# Ethernet.net
KiCad netlist of a schematic drawn in Altium Designer
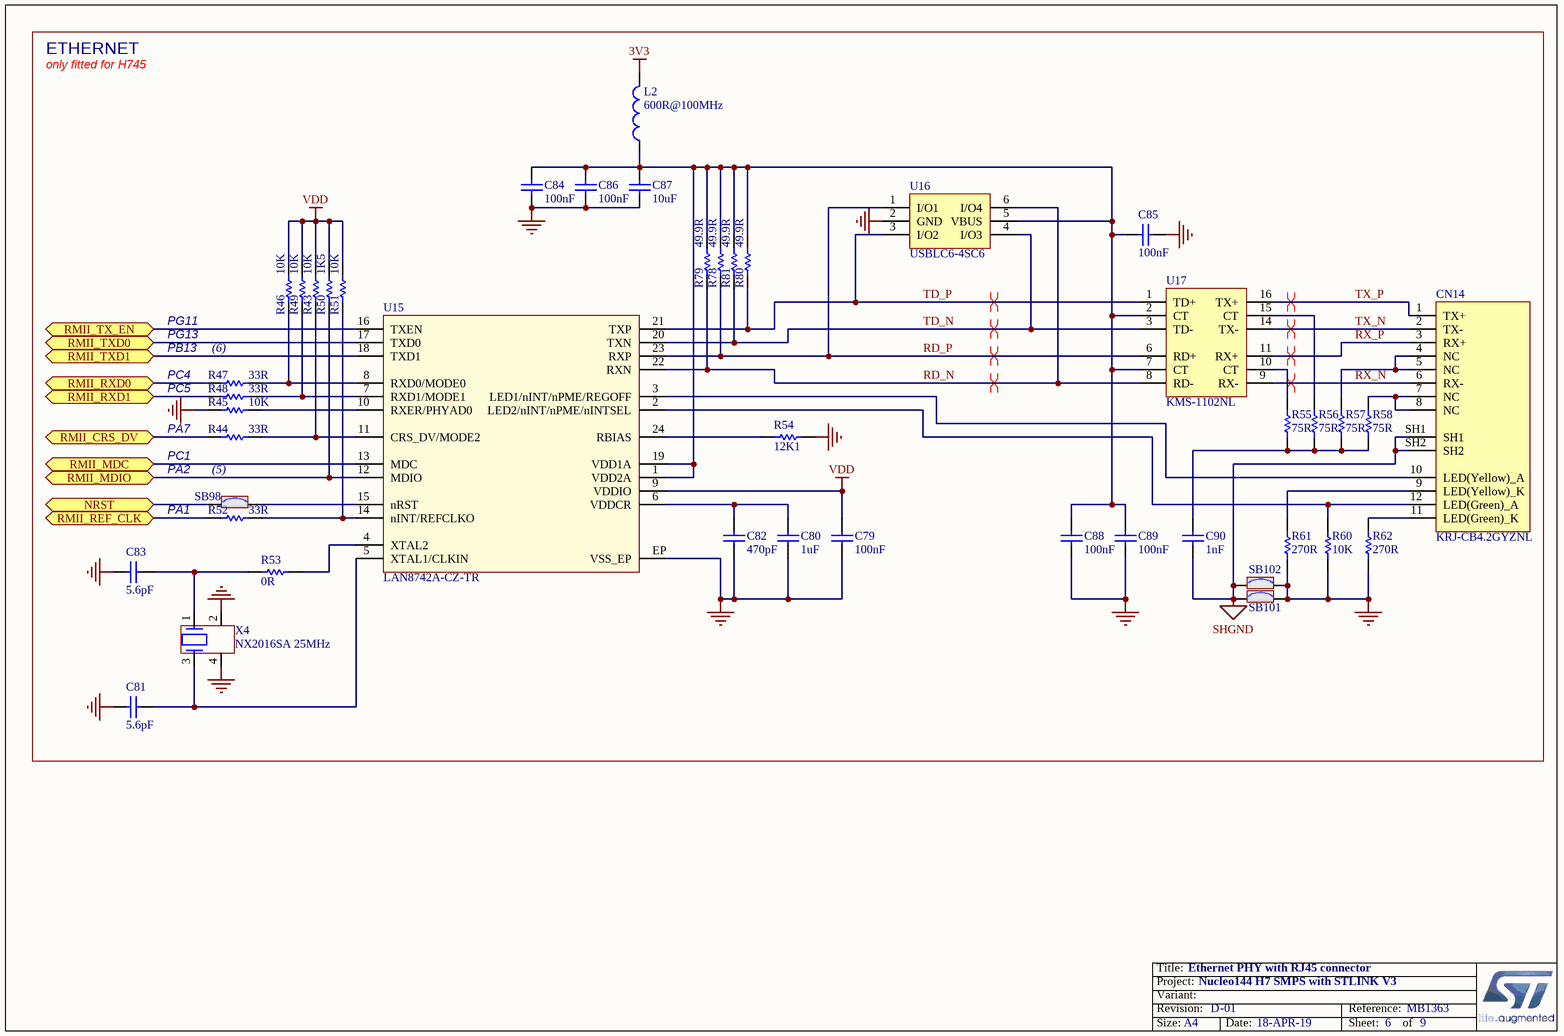
[diagram p0: Ethernet.SchDoc]

(export (version "E")
  (design (tool "Eeschema 10.0.6"))
  (components
    (comp (ref "C79")
      (value "100nF")
      (footprint "C0603")
      (description "Capacitor, MLCC, 100nF, 6V3, X5R, 10%, 0603, T=0,8mm")
      (fields
        (field (name "INTERNAL_PART_NUMBER") "MCD-00237")
        (field (name "MANUFACTURER_PART_NUMBER") "CC0603KRX5R5BB104")
        (field (name "PROVIDED_BY") "SUBCO")
      )
      (libsource (lib "MCD_PARTS_database") (part "Capacitor"))
    )
    (comp (ref "C80")
      (value "1uF")
      (footprint "C0402")
      (description "Capacitor, MLCC, 1uF, 6V3, X5R, 10%, 0402, T=0,5mm")
      (fields
        (field (name "INTERNAL_PART_NUMBER") "MCD-00095")
        (field (name "MANUFACTURER_PART_NUMBER") "GRM155R61E105KA12")
        (field (name "PROVIDED_BY") "SUBCO")
      )
      (libsource (lib "MCD_PARTS_database") (part "Capacitor"))
    )
    (comp (ref "C81")
      (value "5.6pF")
      (footprint "C0402")
      (description "Capacitor, MLCC, 5.6pF, 50V, NPO, 5%, 0402, T=0,5mm")
      (fields
        (field (name "INTERNAL_PART_NUMBER") "MCD-01374")
        (field (name "MANUFACTURER_PART_NUMBER") "CC0402BRNPO9BN5R6")
        (field (name "PROVIDED_BY") "SUBCO")
      )
      (libsource (lib "MCD_PARTS_database") (part "Capacitor"))
    )
    (comp (ref "C82")
      (value "470pF")
      (footprint "C0402")
      (description "Capacitor, MLCC, 470pF, 50V, NPO, 5%, 0402, T=0,5mm")
      (fields
        (field (name "INTERNAL_PART_NUMBER") "MCD-00724")
        (field (name "MANUFACTURER_PART_NUMBER") "CC0402JRNPO9BN471")
        (field (name "PROVIDED_BY") "SUBCO")
      )
      (libsource (lib "MCD_PARTS_database") (part "Capacitor"))
    )
    (comp (ref "C83")
      (value "5.6pF")
      (footprint "C0402")
      (description "Capacitor, MLCC, 5.6pF, 50V, NPO, 5%, 0402, T=0,5mm")
      (fields
        (field (name "INTERNAL_PART_NUMBER") "MCD-01374")
        (field (name "MANUFACTURER_PART_NUMBER") "CC0402BRNPO9BN5R6")
        (field (name "PROVIDED_BY") "SUBCO")
      )
      (libsource (lib "MCD_PARTS_database") (part "Capacitor"))
    )
    (comp (ref "C84")
      (value "100nF")
      (footprint "C0603")
      (description "Capacitor, MLCC, 100nF, 6V3, X5R, 10%, 0603, T=0,8mm")
      (fields
        (field (name "INTERNAL_PART_NUMBER") "MCD-00237")
        (field (name "MANUFACTURER_PART_NUMBER") "CC0603KRX5R5BB104")
        (field (name "PROVIDED_BY") "SUBCO")
      )
      (libsource (lib "MCD_PARTS_database") (part "Capacitor"))
    )
    (comp (ref "C85")
      (value "100nF")
      (footprint "C0603")
      (description "Capacitor, MLCC, 100nF, 6V3, X5R, 10%, 0603, T=0,8mm")
      (fields
        (field (name "INTERNAL_PART_NUMBER") "MCD-00237")
        (field (name "MANUFACTURER_PART_NUMBER") "CC0603KRX5R5BB104")
        (field (name "PROVIDED_BY") "SUBCO")
      )
      (libsource (lib "MCD_PARTS_database") (part "Capacitor"))
    )
    (comp (ref "C86")
      (value "100nF")
      (footprint "C0603")
      (description "Capacitor, MLCC, 100nF, 6V3, X5R, 10%, 0603, T=0,8mm")
      (fields
        (field (name "INTERNAL_PART_NUMBER") "MCD-00237")
        (field (name "MANUFACTURER_PART_NUMBER") "CC0603KRX5R5BB104")
        (field (name "PROVIDED_BY") "SUBCO")
      )
      (libsource (lib "MCD_PARTS_database") (part "Capacitor"))
    )
    (comp (ref "C87")
      (value "10uF")
      (footprint "C0603")
      (description "Capacitor, MLCC, 10µF, 10V, X5R, 10%, 0603, T=0.8mm")
      (fields
        (field (name "INTERNAL_PART_NUMBER") "MCD-01124")
        (field (name "MANUFACTURER_PART_NUMBER") "GRM188R61A106KAAL")
        (field (name "PROVIDED_BY") "SUBCO")
      )
      (libsource (lib "MCD_PARTS_database") (part "Capacitor"))
    )
    (comp (ref "C88")
      (value "100nF")
      (footprint "C0603")
      (description "Capacitor, MLCC, 100nF, 6V3, X5R, 10%, 0603, T=0,8mm")
      (fields
        (field (name "INTERNAL_PART_NUMBER") "MCD-00237")
        (field (name "MANUFACTURER_PART_NUMBER") "CC0603KRX5R5BB104")
        (field (name "PROVIDED_BY") "SUBCO")
      )
      (libsource (lib "MCD_PARTS_database") (part "Capacitor"))
    )
    (comp (ref "C89")
      (value "100nF")
      (footprint "C0603")
      (description "Capacitor, MLCC, 100nF, 6V3, X5R, 10%, 0603, T=0,8mm")
      (fields
        (field (name "INTERNAL_PART_NUMBER") "MCD-00237")
        (field (name "MANUFACTURER_PART_NUMBER") "CC0603KRX5R5BB104")
        (field (name "PROVIDED_BY") "SUBCO")
      )
      (libsource (lib "MCD_PARTS_database") (part "Capacitor"))
    )
    (comp (ref "C90")
      (value "1nF")
      (footprint "C1206_H1P6")
      (description "Capacitor, MLCC, 1nF, 2KV, X7R, 10%, 1206, T=1,25mm")
      (fields
        (field (name "INTERNAL_PART_NUMBER") "MCD-00722")
        (field (name "MANUFACTURER_PART_NUMBER") "CC1206KKX7RDBB102")
        (field (name "PROVIDED_BY") "SUBCO")
      )
      (libsource (lib "MCD_PARTS_database") (part "Capacitor"))
    )
    (comp (ref "CN14")
      (value "KRJ-CB4.2GYZNL")
      (footprint "CON_RJ45_DGKYD_KRJ-CB4.2GYZNL")
      (description "RJ45 jack, single port, with LEDS, Metal shielded dip low profile")
      (fields
        (field (name "INTERNAL_PART_NUMBER") "MCD-00717")
        (field (name "MANUFACTURER") "DONGGUAN KEYOUDA ELECTRONIC TECHNOLOGY")
        (field (name "PROVIDED_BY") "SUBCO")
      )
      (libsource (lib "MCD_PARTS_database") (part "RJ45_KRJ-CB4.2GYZNL"))
    )
    (comp (ref "L2")
      (value "600R@100MHz")
      (footprint "L0603")
      (description "SMD Chip ferrite bead, 600R@100MHz +/-25%, 350mA, 500mohm DC, 0603, T=0.8mm")
      (fields
        (field (name "INTERNAL_PART_NUMBER") "MCD-00047")
        (field (name "MANUFACTURER_PART_NUMBER") "FCM1608KF-601T03")
        (field (name "PROVIDED_BY") "SUBCO")
      )
      (libsource (lib "MCD_PARTS_database") (part "BEAD"))
    )
    (comp (ref "R43")
      (value "10K")
      (footprint "R0402")
      (description "Resistor,10K,0402,1%,1/16W")
      (fields
        (field (name "INTERNAL_PART_NUMBER") "MCD-00053")
        (field (name "MANUFACTURER_PART_NUMBER") "RC0402FR-0710KL")
        (field (name "PROVIDED_BY") "SUBCO")
      )
      (libsource (lib "MCD_PARTS_database") (part "Resistor"))
    )
    (comp (ref "R44")
      (value "33R")
      (footprint "R0402")
      (description "Resistor,33R,0402,1%,1/16W")
      (fields
        (field (name "INTERNAL_PART_NUMBER") "MCD-00455")
        (field (name "MANUFACTURER_PART_NUMBER") "RC0402FR-0733RL")
        (field (name "PROVIDED_BY") "SUBCO")
      )
      (libsource (lib "MCD_PARTS_database") (part "Resistor"))
    )
    (comp (ref "R45")
      (value "10K")
      (footprint "R0402")
      (description "Resistor,10K,0402,1%,1/16W")
      (fields
        (field (name "INTERNAL_PART_NUMBER") "MCD-00053")
        (field (name "MANUFACTURER_PART_NUMBER") "RC0402FR-0710KL")
        (field (name "PROVIDED_BY") "SUBCO")
      )
      (libsource (lib "MCD_PARTS_database") (part "Resistor"))
    )
    (comp (ref "R46")
      (value "10K")
      (footprint "R0402")
      (description "Resistor,10K,0402,1%,1/16W")
      (fields
        (field (name "INTERNAL_PART_NUMBER") "MCD-00053")
        (field (name "MANUFACTURER_PART_NUMBER") "RC0402FR-0710KL")
        (field (name "PROVIDED_BY") "SUBCO")
      )
      (libsource (lib "MCD_PARTS_database") (part "Resistor"))
    )
    (comp (ref "R47")
      (value "33R")
      (footprint "R0402")
      (description "Resistor,33R,0402,1%,1/16W")
      (fields
        (field (name "INTERNAL_PART_NUMBER") "MCD-00455")
        (field (name "MANUFACTURER_PART_NUMBER") "RC0402FR-0733RL")
        (field (name "PROVIDED_BY") "SUBCO")
      )
      (libsource (lib "MCD_PARTS_database") (part "Resistor"))
    )
    (comp (ref "R48")
      (value "33R")
      (footprint "R0402")
      (description "Resistor,33R,0402,1%,1/16W")
      (fields
        (field (name "INTERNAL_PART_NUMBER") "MCD-00455")
        (field (name "MANUFACTURER_PART_NUMBER") "RC0402FR-0733RL")
        (field (name "PROVIDED_BY") "SUBCO")
      )
      (libsource (lib "MCD_PARTS_database") (part "Resistor"))
    )
    (comp (ref "R49")
      (value "10K")
      (footprint "R0402")
      (description "Resistor,10K,0402,1%,1/16W")
      (fields
        (field (name "INTERNAL_PART_NUMBER") "MCD-00053")
        (field (name "MANUFACTURER_PART_NUMBER") "RC0402FR-0710KL")
        (field (name "PROVIDED_BY") "SUBCO")
      )
      (libsource (lib "MCD_PARTS_database") (part "Resistor"))
    )
    (comp (ref "R50")
      (value "1K5")
      (footprint "R0402")
      (description "Resistor,1K5,0402,1%,1/16W")
      (fields
        (field (name "INTERNAL_PART_NUMBER") "MCD-00068")
        (field (name "MANUFACTURER_PART_NUMBER") "RC0402FR-071K5L")
        (field (name "PROVIDED_BY") "SUBCO")
      )
      (libsource (lib "MCD_PARTS_database") (part "Resistor"))
    )
    (comp (ref "R51")
      (value "10K")
      (footprint "R0402")
      (description "Resistor,10K,0402,1%,1/16W")
      (fields
        (field (name "INTERNAL_PART_NUMBER") "MCD-00053")
        (field (name "MANUFACTURER_PART_NUMBER") "RC0402FR-0710KL")
        (field (name "PROVIDED_BY") "SUBCO")
      )
      (libsource (lib "MCD_PARTS_database") (part "Resistor"))
    )
    (comp (ref "R52")
      (value "33R")
      (footprint "R0402")
      (description "Resistor,33R,0402,1%,1/16W")
      (fields
        (field (name "INTERNAL_PART_NUMBER") "MCD-00455")
        (field (name "MANUFACTURER_PART_NUMBER") "RC0402FR-0733RL")
        (field (name "PROVIDED_BY") "SUBCO")
      )
      (libsource (lib "MCD_PARTS_database") (part "Resistor"))
    )
    (comp (ref "R53")
      (value "0R")
      (footprint "R0402")
      (description "Resistor,0R,0402,5%,1/16W")
      (fields
        (field (name "INTERNAL_PART_NUMBER") "MCD-00052")
        (field (name "MANUFACTURER_PART_NUMBER") "RC0402JR-070RL")
        (field (name "PROVIDED_BY") "SUBCO")
      )
      (libsource (lib "MCD_PARTS_database") (part "Resistor"))
    )
    (comp (ref "R54")
      (value "12K1")
      (footprint "R0402")
      (description "Resistor,12K1,0402,1%,1/16W")
      (fields
        (field (name "INTERNAL_PART_NUMBER") "MCD-00723")
        (field (name "MANUFACTURER_PART_NUMBER") "RC0402FR-0712K1L")
        (field (name "PROVIDED_BY") "SUBCO")
      )
      (libsource (lib "MCD_PARTS_database") (part "Resistor"))
    )
    (comp (ref "R55")
      (value "75R")
      (footprint "R0402")
      (description "Resistor,75R,0402,1%,1/16W")
      (fields
        (field (name "INTERNAL_PART_NUMBER") "MCD-00515")
        (field (name "MANUFACTURER_PART_NUMBER") "RC0402FR-0775RL")
        (field (name "PROVIDED_BY") "SUBCO")
      )
      (libsource (lib "MCD_PARTS_database") (part "Resistor"))
    )
    (comp (ref "R56")
      (value "75R")
      (footprint "R0402")
      (description "Resistor,75R,0402,1%,1/16W")
      (fields
        (field (name "INTERNAL_PART_NUMBER") "MCD-00515")
        (field (name "MANUFACTURER_PART_NUMBER") "RC0402FR-0775RL")
        (field (name "PROVIDED_BY") "SUBCO")
      )
      (libsource (lib "MCD_PARTS_database") (part "Resistor"))
    )
    (comp (ref "R57")
      (value "75R")
      (footprint "R0402")
      (description "Resistor,75R,0402,1%,1/16W")
      (fields
        (field (name "INTERNAL_PART_NUMBER") "MCD-00515")
        (field (name "MANUFACTURER_PART_NUMBER") "RC0402FR-0775RL")
        (field (name "PROVIDED_BY") "SUBCO")
      )
      (libsource (lib "MCD_PARTS_database") (part "Resistor"))
    )
    (comp (ref "R58")
      (value "75R")
      (footprint "R0402")
      (description "Resistor,75R,0402,1%,1/16W")
      (fields
        (field (name "INTERNAL_PART_NUMBER") "MCD-00515")
        (field (name "MANUFACTURER_PART_NUMBER") "RC0402FR-0775RL")
        (field (name "PROVIDED_BY") "SUBCO")
      )
      (libsource (lib "MCD_PARTS_database") (part "Resistor"))
    )
    (comp (ref "R60")
      (value "10K")
      (footprint "R0402")
      (description "Resistor,10K,0402,1%,1/16W")
      (fields
        (field (name "INTERNAL_PART_NUMBER") "MCD-00053")
        (field (name "MANUFACTURER_PART_NUMBER") "RC0402FR-0710KL")
        (field (name "PROVIDED_BY") "SUBCO")
      )
      (libsource (lib "MCD_PARTS_database") (part "Resistor"))
    )
    (comp (ref "R61")
      (value "270R")
      (footprint "R0402")
      (description "Resistor,270R,0402,1%,1/16W")
      (fields
        (field (name "INTERNAL_PART_NUMBER") "MCD-00441")
        (field (name "MANUFACTURER_PART_NUMBER") "RC0402FR-07270RL")
        (field (name "PROVIDED_BY") "SUBCO")
      )
      (libsource (lib "MCD_PARTS_database") (part "Resistor"))
    )
    (comp (ref "R62")
      (value "270R")
      (footprint "R0402")
      (description "Resistor,270R,0402,1%,1/16W")
      (fields
        (field (name "INTERNAL_PART_NUMBER") "MCD-00441")
        (field (name "MANUFACTURER_PART_NUMBER") "RC0402FR-07270RL")
        (field (name "PROVIDED_BY") "SUBCO")
      )
      (libsource (lib "MCD_PARTS_database") (part "Resistor"))
    )
    (comp (ref "R78")
      (value "49.9R")
      (footprint "R0402")
      (description "Resistor,49R9,0402,1%,1/16W")
      (fields
        (field (name "INTERNAL_PART_NUMBER") "MCD-00565")
        (field (name "MANUFACTURER_PART_NUMBER") "RC0402FR-0749R9L")
        (field (name "PROVIDED_BY") "SUBCO")
      )
      (libsource (lib "MCD_PARTS_database") (part "Resistor"))
    )
    (comp (ref "R79")
      (value "49.9R")
      (footprint "R0402")
      (description "Resistor,49R9,0402,1%,1/16W")
      (fields
        (field (name "INTERNAL_PART_NUMBER") "MCD-00565")
        (field (name "MANUFACTURER_PART_NUMBER") "RC0402FR-0749R9L")
        (field (name "PROVIDED_BY") "SUBCO")
      )
      (libsource (lib "MCD_PARTS_database") (part "Resistor"))
    )
    (comp (ref "R80")
      (value "49.9R")
      (footprint "R0402")
      (description "Resistor,49R9,0402,1%,1/16W")
      (fields
        (field (name "INTERNAL_PART_NUMBER") "MCD-00565")
        (field (name "MANUFACTURER_PART_NUMBER") "RC0402FR-0749R9L")
        (field (name "PROVIDED_BY") "SUBCO")
      )
      (libsource (lib "MCD_PARTS_database") (part "Resistor"))
    )
    (comp (ref "R81")
      (value "49.9R")
      (footprint "R0402")
      (description "Resistor,49R9,0402,1%,1/16W")
      (fields
        (field (name "INTERNAL_PART_NUMBER") "MCD-00565")
        (field (name "MANUFACTURER_PART_NUMBER") "RC0402FR-0749R9L")
        (field (name "PROVIDED_BY") "SUBCO")
      )
      (libsource (lib "MCD_PARTS_database") (part "Resistor"))
    )
    (comp (ref "SB98")
      (value "SB_ON")
      (footprint "SOLDER-BRIDGE_R0603-0R")
      (description "Solder Bridge ON")
      (fields
        (field (name "INTERNAL_PART_NUMBER") "MCD-00071")
        (field (name "MANUFACTURER_PART_NUMBER") "RC0603JR-070RL")
        (field (name "PROVIDED_BY") "SUBCO")
      )
      (libsource (lib "MCD_PARTS_database") (part "SB_ON"))
    )
    (comp (ref "SB101")
      (value "SB_ON")
      (footprint "SOLDER-BRIDGE_R0603-0R")
      (description "Solder Bridge ON")
      (fields
        (field (name "INTERNAL_PART_NUMBER") "MCD-00071")
        (field (name "MANUFACTURER_PART_NUMBER") "RC0603JR-070RL")
        (field (name "PROVIDED_BY") "SUBCO")
      )
      (libsource (lib "MCD_PARTS_database") (part "SB_ON"))
    )
    (comp (ref "SB102")
      (value "SB_ON")
      (footprint "SOLDER-BRIDGE_R0603-0R")
      (description "Solder Bridge ON")
      (fields
        (field (name "INTERNAL_PART_NUMBER") "MCD-00071")
        (field (name "MANUFACTURER_PART_NUMBER") "RC0603JR-070RL")
        (field (name "PROVIDED_BY") "SUBCO")
      )
      (libsource (lib "MCD_PARTS_database") (part "SB_ON"))
    )
    (comp (ref "U15")
      (value "LAN8742A-CZ-TR")
      (footprint "ICC_VQFN24-EPAD_4X4_P050")
      (description "10/100M RMII Ethernet transceiver")
      (fields
        (field (name "INTERNAL_PART_NUMBER") "MCD-00719")
        (field (name "MANUFACTURER") "MICROCHIP")
        (field (name "PROVIDED_BY") "SUBCO")
      )
      (libsource (lib "MCD_PARTS_database") (part "LAN8742A-CZ-TR"))
    )
    (comp (ref "U16")
      (value "USBLC6-4SC6")
      (footprint "ESD_SOT23-6L")
      (description "Very low capacitance ESD protection , 4 lines")
      (fields
        (field (name "INTERNAL_PART_NUMBER") "MCD-00250")
        (field (name "MANUFACTURER") "STMICROELECTRONICS")
        (field (name "PROVIDED_BY") "SUBCO with ST control")
      )
      (libsource (lib "MCD_PARTS_database") (part "USBLC6-4SC6"))
    )
    (comp (ref "U17")
      (value "KMS-1102NL")
      (footprint "TRS_DGKYD_KMS-1102NL")
      (description "Discrete Magnetic Transformer Module, 16 pins, SMT, 100 Base-TX")
      (fields
        (field (name "INTERNAL_PART_NUMBER") "MCD-00718")
        (field (name "MANUFACTURER") "DONGGUAN KEYOUDA ELECTRONIC TECHNOLOGY")
        (field (name "PROVIDED_BY") "SUBCO")
      )
      (libsource (lib "MCD_PARTS_database") (part "KMS-1102NL"))
    )
    (comp (ref "X4")
      (value "NX2016SA 25MHz")
      (footprint "CRY_NX2016SA_4P")
      (description "Crystal 25MHz, 6pF, +-20ppm, 80ohms max, SMD")
      (fields
        (field (name "INTERNAL_PART_NUMBER") "MCD-01364")
        (field (name "MANUFACTURER_PART_NUMBER") "NX2016SA 25MHz EXS00A-CS11321")
        (field (name "PROVIDED_BY") "SUBCO")
      )
      (libsource (lib "MCD_PARTS_database") (part "XTAL_4_PINS"))
    )
  )
  (nets
    (net (code "1") (name "/NRST") (class "Default")
      (node (ref "SB98") (pin "1") (pinfunction "1_1") (pintype "passive"))
    )
    (net (code "2") (name "/RD_N") (class "Default")
      (node (ref "R79") (pin "1") (pinfunction "1_1") (pintype "passive"))
      (node (ref "U15") (pin "22") (pinfunction "RXN_22") (pintype "passive"))
      (node (ref "U16") (pin "6") (pinfunction "I/O4_6") (pintype "passive"))
      (node (ref "U17") (pin "8") (pinfunction "RD-_8") (pintype "passive"))
    )
    (net (code "3") (name "/RD_P") (class "Default")
      (node (ref "R78") (pin "1") (pinfunction "1_1") (pintype "passive"))
      (node (ref "U15") (pin "23") (pinfunction "RXP_23") (pintype "passive"))
      (node (ref "U16") (pin "1") (pinfunction "I/O1_1") (pintype "passive"))
      (node (ref "U17") (pin "6") (pinfunction "RD+_6") (pintype "passive"))
    )
    (net (code "4") (name "/RMII_CRS_DV") (class "Default")
      (node (ref "R44") (pin "1") (pinfunction "1_1") (pintype "passive"))
    )
    (net (code "5") (name "/RMII_MDC") (class "Default")
      (node (ref "U15") (pin "13") (pinfunction "MDC_13") (pintype "passive"))
    )
    (net (code "6") (name "/RMII_MDIO") (class "Default")
      (node (ref "R50") (pin "1") (pinfunction "1_1") (pintype "passive"))
      (node (ref "U15") (pin "12") (pinfunction "MDIO_12") (pintype "passive"))
    )
    (net (code "7") (name "/RMII_REF_CLK") (class "Default")
      (node (ref "R52") (pin "1") (pinfunction "1_1") (pintype "passive"))
    )
    (net (code "8") (name "/RMII_RXD0") (class "Default")
      (node (ref "R47") (pin "1") (pinfunction "1_1") (pintype "passive"))
    )
    (net (code "9") (name "/RMII_RXD1") (class "Default")
      (node (ref "R48") (pin "1") (pinfunction "1_1") (pintype "passive"))
    )
    (net (code "10") (name "/RMII_TXD0") (class "Default")
      (node (ref "U15") (pin "17") (pinfunction "TXD0_17") (pintype "passive"))
    )
    (net (code "11") (name "/RMII_TXD1") (class "Default")
      (node (ref "U15") (pin "18") (pinfunction "TXD1_18") (pintype "passive"))
    )
    (net (code "12") (name "/RMII_TX_EN") (class "Default")
      (node (ref "U15") (pin "16") (pinfunction "TXEN_16") (pintype "passive"))
    )
    (net (code "13") (name "/RX_N") (class "Default")
      (node (ref "CN14") (pin "6") (pinfunction "RX-_6") (pintype "passive"))
      (node (ref "U17") (pin "9") (pinfunction "RX-_9") (pintype "passive"))
    )
    (net (code "14") (name "/RX_P") (class "Default")
      (node (ref "CN14") (pin "3") (pinfunction "RX+_3") (pintype "passive"))
      (node (ref "U17") (pin "11") (pinfunction "RX+_11") (pintype "passive"))
    )
    (net (code "15") (name "/TD_N") (class "Default")
      (node (ref "R81") (pin "1") (pinfunction "1_1") (pintype "passive"))
      (node (ref "U15") (pin "20") (pinfunction "TXN_20") (pintype "passive"))
      (node (ref "U16") (pin "4") (pinfunction "I/O3_4") (pintype "passive"))
      (node (ref "U17") (pin "3") (pinfunction "TD-_3") (pintype "passive"))
    )
    (net (code "16") (name "/TD_P") (class "Default")
      (node (ref "R80") (pin "1") (pinfunction "1_1") (pintype "passive"))
      (node (ref "U15") (pin "21") (pinfunction "TXP_21") (pintype "passive"))
      (node (ref "U16") (pin "3") (pinfunction "I/O2_3") (pintype "passive"))
      (node (ref "U17") (pin "1") (pinfunction "TD+_1") (pintype "passive"))
    )
    (net (code "17") (name "/TX_N") (class "Default")
      (node (ref "CN14") (pin "2") (pinfunction "TX-_2") (pintype "passive"))
      (node (ref "U17") (pin "14") (pinfunction "TX-_14") (pintype "passive"))
    )
    (net (code "18") (name "/TX_P") (class "Default")
      (node (ref "CN14") (pin "1") (pinfunction "TX+_1") (pintype "passive"))
      (node (ref "U17") (pin "16") (pinfunction "TX+_16") (pintype "passive"))
    )
    (net (code "19") (name "3V3") (class "Default")
      (node (ref "L2") (pin "2") (pinfunction "2_2") (pintype "passive"))
    )
    (net (code "20") (name "GND") (class "Default")
      (node (ref "C79") (pin "1") (pinfunction "1_1") (pintype "passive"))
      (node (ref "C80") (pin "1") (pinfunction "1_1") (pintype "passive"))
      (node (ref "C81") (pin "1") (pinfunction "1_1") (pintype "passive"))
      (node (ref "C82") (pin "1") (pinfunction "1_1") (pintype "passive"))
      (node (ref "C83") (pin "1") (pinfunction "1_1") (pintype "passive"))
      (node (ref "C84") (pin "1") (pinfunction "1_1") (pintype "passive"))
      (node (ref "C85") (pin "2") (pinfunction "2_2") (pintype "passive"))
      (node (ref "C86") (pin "1") (pinfunction "1_1") (pintype "passive"))
      (node (ref "C87") (pin "1") (pinfunction "1_1") (pintype "passive"))
      (node (ref "C88") (pin "1") (pinfunction "1_1") (pintype "passive"))
      (node (ref "C89") (pin "1") (pinfunction "1_1") (pintype "passive"))
      (node (ref "R45") (pin "2") (pinfunction "2_2") (pintype "passive"))
      (node (ref "R54") (pin "2") (pinfunction "2_2") (pintype "passive"))
      (node (ref "R60") (pin "1") (pinfunction "1_1") (pintype "passive"))
      (node (ref "R61") (pin "1") (pinfunction "1_1") (pintype "passive"))
      (node (ref "R62") (pin "1") (pinfunction "1_1") (pintype "passive"))
      (node (ref "SB101") (pin "2") (pinfunction "2_2") (pintype "passive"))
      (node (ref "SB102") (pin "2") (pinfunction "2_2") (pintype "passive"))
      (node (ref "U15") (pin "EP") (pinfunction "VSS_EP_EP") (pintype "passive"))
      (node (ref "U16") (pin "2") (pinfunction "GND_2") (pintype "passive"))
      (node (ref "X4") (pin "2") (pinfunction "2_2") (pintype "passive"))
      (node (ref "X4") (pin "4") (pinfunction "4_4") (pintype "passive"))
    )
    (net (code "21") (name "Net-(C83-Pad2)") (class "Default")
      (node (ref "C83") (pin "2") (pinfunction "2_2") (pintype "passive"))
      (node (ref "R53") (pin "1") (pinfunction "1_1") (pintype "passive"))
      (node (ref "X4") (pin "1") (pinfunction "1_1") (pintype "passive"))
    )
    (net (code "22") (name "Net-(C90-Pad2)") (class "Default")
      (node (ref "C90") (pin "2") (pinfunction "2_2") (pintype "passive"))
      (node (ref "R55") (pin "1") (pinfunction "1_1") (pintype "passive"))
      (node (ref "R56") (pin "1") (pinfunction "1_1") (pintype "passive"))
      (node (ref "R57") (pin "1") (pinfunction "1_1") (pintype "passive"))
      (node (ref "R58") (pin "1") (pinfunction "1_1") (pintype "passive"))
    )
    (net (code "23") (name "Net-(CN14-LED(Green)_A)") (class "Default")
      (node (ref "CN14") (pin "12") (pinfunction "LED(Green)_A_12") (pintype "passive"))
      (node (ref "R60") (pin "2") (pinfunction "2_2") (pintype "passive"))
      (node (ref "U15") (pin "2") (pinfunction "LED2/nINT/nPME/nINTSEL_2") (pintype "passive"))
    )
    (net (code "24") (name "Net-(CN14-LED(Green)_K)") (class "Default")
      (node (ref "CN14") (pin "11") (pinfunction "LED(Green)_K_11") (pintype "passive"))
      (node (ref "R62") (pin "2") (pinfunction "2_2") (pintype "passive"))
    )
    (net (code "25") (name "Net-(CN14-LED(Yellow)_A)") (class "Default")
      (node (ref "CN14") (pin "10") (pinfunction "LED(Yellow)_A_10") (pintype "passive"))
      (node (ref "U15") (pin "3") (pinfunction "LED1/nINT/nPME/REGOFF_3") (pintype "passive"))
    )
    (net (code "26") (name "Net-(CN14-LED(Yellow)_K)") (class "Default")
      (node (ref "CN14") (pin "9") (pinfunction "LED(Yellow)_K_9") (pintype "passive"))
      (node (ref "R61") (pin "2") (pinfunction "2_2") (pintype "passive"))
    )
    (net (code "27") (name "Net-(CN14-NC-Pad4)") (class "Default")
      (node (ref "CN14") (pin "4") (pinfunction "NC_4") (pintype "passive"))
      (node (ref "CN14") (pin "5") (pinfunction "NC_5") (pintype "passive"))
      (node (ref "R57") (pin "2") (pinfunction "2_2") (pintype "passive"))
    )
    (net (code "28") (name "Net-(CN14-NC-Pad7)") (class "Default")
      (node (ref "CN14") (pin "7") (pinfunction "NC_7") (pintype "passive"))
      (node (ref "CN14") (pin "8") (pinfunction "NC_8") (pintype "passive"))
      (node (ref "R58") (pin "2") (pinfunction "2_2") (pintype "passive"))
    )
    (net (code "29") (name "Net-(R55-Pad2)") (class "Default")
      (node (ref "R55") (pin "2") (pinfunction "2_2") (pintype "passive"))
      (node (ref "U17") (pin "10") (pinfunction "CT_10") (pintype "passive"))
    )
    (net (code "30") (name "Net-(R56-Pad2)") (class "Default")
      (node (ref "R56") (pin "2") (pinfunction "2_2") (pintype "passive"))
      (node (ref "U17") (pin "15") (pinfunction "CT_15") (pintype "passive"))
    )
    (net (code "31") (name "Net-(U15-CRS_DV{slash}MODE2)") (class "Default")
      (node (ref "R43") (pin "1") (pinfunction "1_1") (pintype "passive"))
      (node (ref "R44") (pin "2") (pinfunction "2_2") (pintype "passive"))
      (node (ref "U15") (pin "11") (pinfunction "CRS_DV/MODE2_11") (pintype "passive"))
    )
    (net (code "32") (name "Net-(U15-RBIAS)") (class "Default")
      (node (ref "R54") (pin "1") (pinfunction "1_1") (pintype "passive"))
      (node (ref "U15") (pin "24") (pinfunction "RBIAS_24") (pintype "passive"))
    )
    (net (code "33") (name "Net-(U15-RXD0{slash}MODE0)") (class "Default")
      (node (ref "R46") (pin "1") (pinfunction "1_1") (pintype "passive"))
      (node (ref "R47") (pin "2") (pinfunction "2_2") (pintype "passive"))
      (node (ref "U15") (pin "8") (pinfunction "RXD0/MODE0_8") (pintype "passive"))
    )
    (net (code "34") (name "Net-(U15-RXD1{slash}MODE1)") (class "Default")
      (node (ref "R48") (pin "2") (pinfunction "2_2") (pintype "passive"))
      (node (ref "R49") (pin "1") (pinfunction "1_1") (pintype "passive"))
      (node (ref "U15") (pin "7") (pinfunction "RXD1/MODE1_7") (pintype "passive"))
    )
    (net (code "35") (name "Net-(U15-RXER{slash}PHYAD0)") (class "Default")
      (node (ref "R45") (pin "1") (pinfunction "1_1") (pintype "passive"))
      (node (ref "U15") (pin "10") (pinfunction "RXER/PHYAD0_10") (pintype "passive"))
    )
    (net (code "36") (name "Net-(U15-VDD1A)") (class "Default")
      (node (ref "C84") (pin "2") (pinfunction "2_2") (pintype "passive"))
      (node (ref "C85") (pin "1") (pinfunction "1_1") (pintype "passive"))
      (node (ref "C86") (pin "2") (pinfunction "2_2") (pintype "passive"))
      (node (ref "C87") (pin "2") (pinfunction "2_2") (pintype "passive"))
      (node (ref "C88") (pin "2") (pinfunction "2_2") (pintype "passive"))
      (node (ref "C89") (pin "2") (pinfunction "2_2") (pintype "passive"))
      (node (ref "L2") (pin "1") (pinfunction "1_1") (pintype "passive"))
      (node (ref "R78") (pin "2") (pinfunction "2_2") (pintype "passive"))
      (node (ref "R79") (pin "2") (pinfunction "2_2") (pintype "passive"))
      (node (ref "R80") (pin "2") (pinfunction "2_2") (pintype "passive"))
      (node (ref "R81") (pin "2") (pinfunction "2_2") (pintype "passive"))
      (node (ref "U15") (pin "1") (pinfunction "VDD2A_1") (pintype "passive"))
      (node (ref "U15") (pin "19") (pinfunction "VDD1A_19") (pintype "passive"))
      (node (ref "U16") (pin "5") (pinfunction "VBUS_5") (pintype "passive"))
      (node (ref "U17") (pin "2") (pinfunction "CT_2") (pintype "passive"))
      (node (ref "U17") (pin "7") (pinfunction "CT_7") (pintype "passive"))
    )
    (net (code "37") (name "Net-(U15-VDDCR)") (class "Default")
      (node (ref "C80") (pin "2") (pinfunction "2_2") (pintype "passive"))
      (node (ref "C82") (pin "2") (pinfunction "2_2") (pintype "passive"))
      (node (ref "U15") (pin "6") (pinfunction "VDDCR_6") (pintype "passive"))
    )
    (net (code "38") (name "Net-(U15-XTAL1{slash}CLKIN)") (class "Default")
      (node (ref "C81") (pin "2") (pinfunction "2_2") (pintype "passive"))
      (node (ref "U15") (pin "5") (pinfunction "XTAL1/CLKIN_5") (pintype "passive"))
      (node (ref "X4") (pin "3") (pinfunction "3_3") (pintype "passive"))
    )
    (net (code "39") (name "Net-(U15-XTAL2)") (class "Default")
      (node (ref "R53") (pin "2") (pinfunction "2_2") (pintype "passive"))
      (node (ref "U15") (pin "4") (pinfunction "XTAL2_4") (pintype "passive"))
    )
    (net (code "40") (name "Net-(U15-nINT{slash}REFCLKO)") (class "Default")
      (node (ref "R51") (pin "1") (pinfunction "1_1") (pintype "passive"))
      (node (ref "R52") (pin "2") (pinfunction "2_2") (pintype "passive"))
      (node (ref "U15") (pin "14") (pinfunction "nINT/REFCLKO_14") (pintype "passive"))
    )
    (net (code "41") (name "Net-(U15-nRST)") (class "Default")
      (node (ref "SB98") (pin "2") (pinfunction "2_2") (pintype "passive"))
      (node (ref "U15") (pin "15") (pinfunction "nRST_15") (pintype "passive"))
    )
    (net (code "42") (name "SHGND") (class "Default")
      (node (ref "C90") (pin "1") (pinfunction "1_1") (pintype "passive"))
      (node (ref "CN14") (pin "SH1") (pinfunction "SH1_SH1") (pintype "passive"))
      (node (ref "CN14") (pin "SH2") (pinfunction "SH2_SH2") (pintype "passive"))
      (node (ref "SB101") (pin "1") (pinfunction "1_1") (pintype "passive"))
      (node (ref "SB102") (pin "1") (pinfunction "1_1") (pintype "passive"))
    )
    (net (code "43") (name "VDD") (class "Default")
      (node (ref "C79") (pin "2") (pinfunction "2_2") (pintype "passive"))
      (node (ref "R43") (pin "2") (pinfunction "2_2") (pintype "passive"))
      (node (ref "R46") (pin "2") (pinfunction "2_2") (pintype "passive"))
      (node (ref "R49") (pin "2") (pinfunction "2_2") (pintype "passive"))
      (node (ref "R50") (pin "2") (pinfunction "2_2") (pintype "passive"))
      (node (ref "R51") (pin "2") (pinfunction "2_2") (pintype "passive"))
      (node (ref "U15") (pin "9") (pinfunction "VDDIO_9") (pintype "passive"))
    )
  )
)
